# BOSS-Ion-Pump-Interface.net
KiCad netlist of a schematic drawn in EAGLE
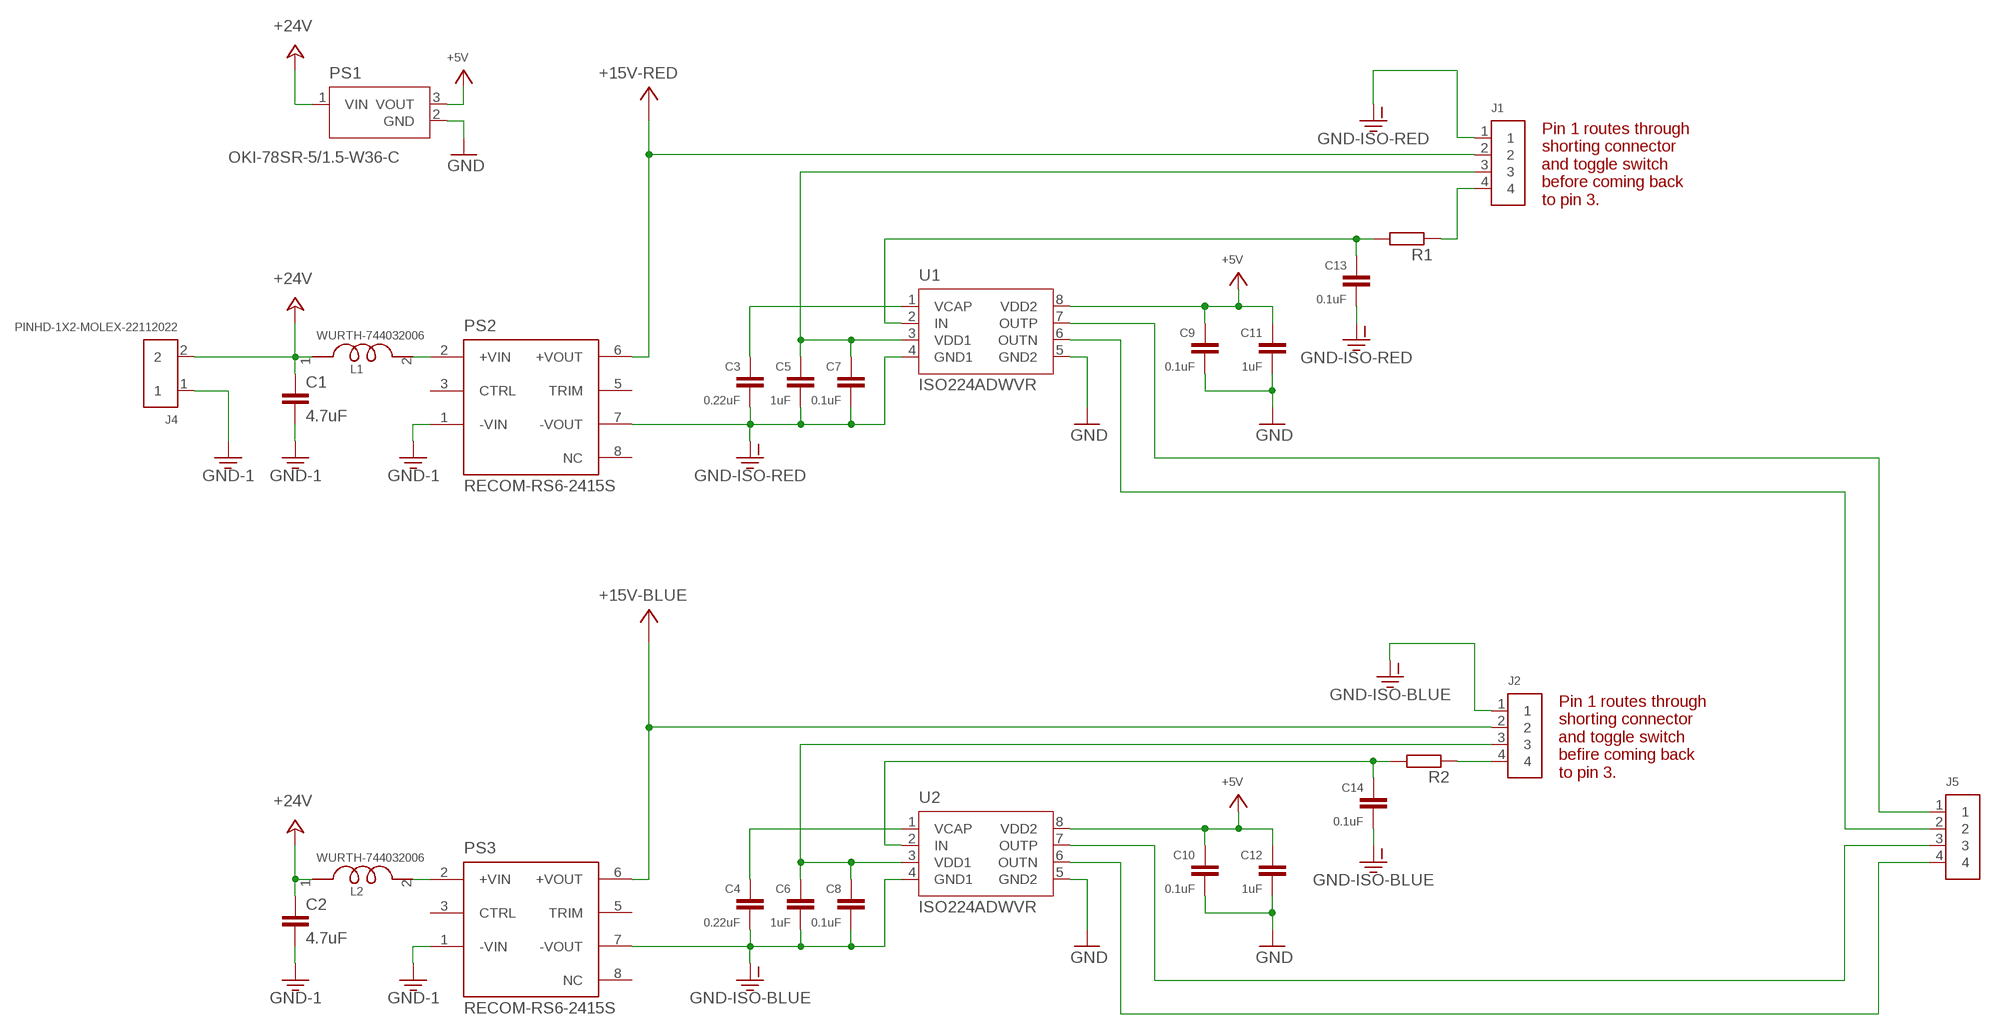
[diagram p0: schematic, sheet 1]

(export (version "E")
  (design (tool "Eeschema 10.0.6"))
  (components
    (comp (ref "C1")
      (value "4.7uF")
      (footprint "eagle-import:C1206")
      (libsource (lib "eagle-import") (part "C-EUC1206"))
    )
    (comp (ref "C2")
      (value "4.7uF")
      (footprint "eagle-import:C1206")
      (libsource (lib "eagle-import") (part "C-EUC1206"))
    )
    (comp (ref "C3")
      (value "0.22uF")
      (footprint "eagle-import:C0805")
      (libsource (lib "eagle-import") (part "C-EUC0805"))
    )
    (comp (ref "C4")
      (value "0.22uF")
      (footprint "eagle-import:C0805")
      (libsource (lib "eagle-import") (part "C-EUC0805"))
    )
    (comp (ref "C5")
      (value "1uF")
      (footprint "eagle-import:C0805")
      (libsource (lib "eagle-import") (part "C-EUC0805"))
    )
    (comp (ref "C6")
      (value "1uF")
      (footprint "eagle-import:C0805")
      (libsource (lib "eagle-import") (part "C-EUC0805"))
    )
    (comp (ref "C7")
      (value "0.1uF")
      (footprint "eagle-import:C0805")
      (libsource (lib "eagle-import") (part "C-EUC0805"))
    )
    (comp (ref "C8")
      (value "0.1uF")
      (footprint "eagle-import:C0805")
      (libsource (lib "eagle-import") (part "C-EUC0805"))
    )
    (comp (ref "C9")
      (value "0.1uF")
      (footprint "eagle-import:C0805")
      (libsource (lib "eagle-import") (part "C-EUC0805"))
    )
    (comp (ref "C10")
      (value "0.1uF")
      (footprint "eagle-import:C0805")
      (libsource (lib "eagle-import") (part "C-EUC0805"))
    )
    (comp (ref "C11")
      (value "1uF")
      (footprint "eagle-import:C0805")
      (libsource (lib "eagle-import") (part "C-EUC0805"))
    )
    (comp (ref "C12")
      (value "1uF")
      (footprint "eagle-import:C0805")
      (libsource (lib "eagle-import") (part "C-EUC0805"))
    )
    (comp (ref "C13")
      (value "0.1uF")
      (footprint "eagle-import:C0805")
      (libsource (lib "eagle-import") (part "C-EUC0805"))
    )
    (comp (ref "C14")
      (value "0.1uF")
      (footprint "eagle-import:C0805")
      (libsource (lib "eagle-import") (part "C-EUC0805"))
    )
    (comp (ref "J1")
      (value "PINHD-1X4-MOLEX-22112042")
      (footprint "eagle-import:1X04-MOLEX-22112042")
      (libsource (lib "eagle-import") (part "PINHD-1X4-MOLEX-22112042"))
    )
    (comp (ref "J2")
      (value "PINHD-1X4-MOLEX-22112042")
      (footprint "eagle-import:1X04-MOLEX-22112042")
      (libsource (lib "eagle-import") (part "PINHD-1X4-MOLEX-22112042"))
    )
    (comp (ref "J4")
      (value "PINHD-1X2-MOLEX-22112022")
      (footprint "eagle-import:1X02-MOLEX-22112022")
      (libsource (lib "eagle-import") (part "PINHD-1X2-MOLEX-22112022"))
    )
    (comp (ref "J5")
      (value "PINHD-1X4-MOLEX-22112042")
      (footprint "eagle-import:1X04-MOLEX-22112042")
      (libsource (lib "eagle-import") (part "PINHD-1X4-MOLEX-22112042"))
    )
    (comp (ref "L1")
      (value "WURTH-744032006")
      (footprint "eagle-import:WURTH-1210-INDUCTOR")
      (libsource (lib "eagle-import") (part "INDUCTOR-WURTH-744032006"))
    )
    (comp (ref "L2")
      (value "WURTH-744032006")
      (footprint "eagle-import:WURTH-1210-INDUCTOR")
      (libsource (lib "eagle-import") (part "INDUCTOR-WURTH-744032006"))
    )
    (comp (ref "PS1")
      (value "OKI-78SR-5/1.5-W36-C")
      (footprint "eagle-import:CONV_OKI-78SR-5_1.5-W36-C")
      (fields
        (field (name "DIGI-KEY_PART_NUMBER") "811-2196-5-ND")
        (field (name "MF") "Murata Power Solutions Inc.")
      )
      (libsource (lib "eagle-import") (part "OKI-78SR-5/1.5-W36-C"))
    )
    (comp (ref "PS2")
      (value "RECOM-RS6-2415S")
      (footprint "eagle-import:CONV_RS6-2415S")
      (fields
        (field (name "DIGI-KEY_PART_NUMBER") "945-2987-ND")
        (field (name "MF") "Recom Power")
        (field (name "MP") "RS6-2415S")
      )
      (libsource (lib "eagle-import") (part "DC-DC-15V-RECOM-RS6-2415S"))
    )
    (comp (ref "PS3")
      (value "RECOM-RS6-2415S")
      (footprint "eagle-import:CONV_RS6-2415S")
      (fields
        (field (name "DIGI-KEY_PART_NUMBER") "945-2987-ND")
        (field (name "MF") "Recom Power")
        (field (name "MP") "RS6-2415S")
      )
      (libsource (lib "eagle-import") (part "DC-DC-15V-RECOM-RS6-2415S"))
    )
    (comp (ref "R1")
      (value "R-EU_R0805")
      (footprint "eagle-import:R0805")
      (libsource (lib "eagle-import") (part "R-EU_R0805"))
    )
    (comp (ref "R2")
      (value "R-EU_R0805")
      (footprint "eagle-import:R0805")
      (libsource (lib "eagle-import") (part "R-EU_R0805"))
    )
    (comp (ref "U1")
      (value "ISO224ADWVR")
      (footprint "eagle-import:DWV8_TEX")
      (fields (field (name "COPYRIGHT") "Copyright (C) 2018 Accelerated Designs. All rights reserved"))
      (libsource (lib "eagle-import") (part "ISO224ADWVR"))
    )
    (comp (ref "U2")
      (value "ISO224ADWVR")
      (footprint "eagle-import:DWV8_TEX")
      (fields (field (name "COPYRIGHT") "Copyright (C) 2018 Accelerated Designs. All rights reserved"))
      (libsource (lib "eagle-import") (part "ISO224ADWVR"))
    )
  )
  (nets
    (net (code "1") (name "+5V") (class "Default")
      (node (ref "C10") (pin "1") (pinfunction "1_1") (pintype "passive"))
      (node (ref "C11") (pin "1") (pinfunction "1_1") (pintype "passive"))
      (node (ref "C12") (pin "1") (pinfunction "1_1") (pintype "passive"))
      (node (ref "C9") (pin "1") (pinfunction "1_1") (pintype "passive"))
      (node (ref "PS1") (pin "3") (pinfunction "VOUT_3") (pintype "power_in"))
      (node (ref "U1") (pin "8") (pinfunction "VDD2_8") (pintype "power_in"))
      (node (ref "U2") (pin "8") (pinfunction "VDD2_8") (pintype "power_in"))
    )
    (net (code "2") (name "+15V-BLUE") (class "Default")
      (node (ref "J2") (pin "2") (pinfunction "2_2") (pintype "bidirectional"))
      (node (ref "PS3") (pin "6") (pinfunction "+VOUT_6") (pintype "output"))
    )
    (net (code "3") (name "+15V-RED") (class "Default")
      (node (ref "J1") (pin "2") (pinfunction "2_2") (pintype "bidirectional"))
      (node (ref "PS2") (pin "6") (pinfunction "+VOUT_6") (pintype "output"))
    )
    (net (code "4") (name "+24V") (class "Default")
      (node (ref "C1") (pin "1") (pinfunction "1_1") (pintype "passive"))
      (node (ref "C2") (pin "1") (pinfunction "1_1") (pintype "passive"))
      (node (ref "J4") (pin "2") (pinfunction "2_2") (pintype "bidirectional"))
      (node (ref "L1") (pin "1") (pinfunction "1_1") (pintype "bidirectional"))
      (node (ref "L2") (pin "1") (pinfunction "1_1") (pintype "bidirectional"))
      (node (ref "PS1") (pin "1") (pinfunction "VIN_1") (pintype "input"))
    )
    (net (code "5") (name "GND") (class "Default")
      (node (ref "C10") (pin "2") (pinfunction "2_2") (pintype "passive"))
      (node (ref "C11") (pin "2") (pinfunction "2_2") (pintype "passive"))
      (node (ref "C12") (pin "2") (pinfunction "2_2") (pintype "passive"))
      (node (ref "C9") (pin "2") (pinfunction "2_2") (pintype "passive"))
      (node (ref "PS1") (pin "2") (pinfunction "GND_2") (pintype "power_in"))
      (node (ref "U1") (pin "5") (pinfunction "GND2_5") (pintype "power_in"))
      (node (ref "U2") (pin "5") (pinfunction "GND2_5") (pintype "power_in"))
    )
    (net (code "6") (name "GND-1") (class "Default")
      (node (ref "C1") (pin "2") (pinfunction "2_2") (pintype "passive"))
      (node (ref "C2") (pin "2") (pinfunction "2_2") (pintype "passive"))
      (node (ref "J4") (pin "1") (pinfunction "1_1") (pintype "bidirectional"))
      (node (ref "PS2") (pin "1") (pinfunction "-VIN_1") (pintype "input"))
      (node (ref "PS3") (pin "1") (pinfunction "-VIN_1") (pintype "input"))
    )
    (net (code "7") (name "GND-ISO-BLUE") (class "Default")
      (node (ref "C14") (pin "2") (pinfunction "2_2") (pintype "passive"))
      (node (ref "C4") (pin "2") (pinfunction "2_2") (pintype "passive"))
      (node (ref "C6") (pin "2") (pinfunction "2_2") (pintype "passive"))
      (node (ref "C8") (pin "2") (pinfunction "2_2") (pintype "passive"))
      (node (ref "J2") (pin "1") (pinfunction "1_1") (pintype "bidirectional"))
      (node (ref "PS3") (pin "7") (pinfunction "-VOUT_7") (pintype "output"))
      (node (ref "U2") (pin "4") (pinfunction "GND1_4") (pintype "power_in"))
    )
    (net (code "8") (name "GND-ISO-RED") (class "Default")
      (node (ref "C13") (pin "2") (pinfunction "2_2") (pintype "passive"))
      (node (ref "C3") (pin "2") (pinfunction "2_2") (pintype "passive"))
      (node (ref "C5") (pin "2") (pinfunction "2_2") (pintype "passive"))
      (node (ref "C7") (pin "2") (pinfunction "2_2") (pintype "passive"))
      (node (ref "J1") (pin "1") (pinfunction "1_1") (pintype "bidirectional"))
      (node (ref "PS2") (pin "7") (pinfunction "-VOUT_7") (pintype "output"))
      (node (ref "U1") (pin "4") (pinfunction "GND1_4") (pintype "power_in"))
    )
    (net (code "9") (name "Net-(J1-Pad4)") (class "Default")
      (node (ref "J1") (pin "4") (pinfunction "4_4") (pintype "bidirectional"))
      (node (ref "R1") (pin "1") (pinfunction "1_1") (pintype "passive"))
    )
    (net (code "10") (name "Net-(J2-Pad4)") (class "Default")
      (node (ref "J2") (pin "4") (pinfunction "4_4") (pintype "bidirectional"))
      (node (ref "R2") (pin "1") (pinfunction "1_1") (pintype "passive"))
    )
    (net (code "11") (name "Net-(PS2-+VIN)") (class "Default")
      (node (ref "L1") (pin "2") (pinfunction "2_2") (pintype "bidirectional"))
      (node (ref "PS2") (pin "2") (pinfunction "+VIN_2") (pintype "input"))
    )
    (net (code "12") (name "Net-(PS3-+VIN)") (class "Default")
      (node (ref "L2") (pin "2") (pinfunction "2_2") (pintype "bidirectional"))
      (node (ref "PS3") (pin "2") (pinfunction "+VIN_2") (pintype "input"))
    )
    (net (code "13") (name "Net-(U1-IN)") (class "Default")
      (node (ref "C13") (pin "1") (pinfunction "1_1") (pintype "passive"))
      (node (ref "R1") (pin "2") (pinfunction "2_2") (pintype "passive"))
      (node (ref "U1") (pin "2") (pinfunction "IN_2") (pintype "input"))
    )
    (net (code "14") (name "Net-(U1-OUTN)") (class "Default")
      (node (ref "J5") (pin "2") (pinfunction "2_2") (pintype "bidirectional"))
      (node (ref "U1") (pin "6") (pinfunction "OUTN_6") (pintype "output"))
    )
    (net (code "15") (name "Net-(U1-OUTP)") (class "Default")
      (node (ref "J5") (pin "1") (pinfunction "1_1") (pintype "bidirectional"))
      (node (ref "U1") (pin "7") (pinfunction "OUTP_7") (pintype "output"))
    )
    (net (code "16") (name "Net-(U1-VCAP)") (class "Default")
      (node (ref "C3") (pin "1") (pinfunction "1_1") (pintype "passive"))
      (node (ref "U1") (pin "1") (pinfunction "VCAP_1") (pintype "power_in"))
    )
    (net (code "17") (name "Net-(U1-VDD1)") (class "Default")
      (node (ref "C5") (pin "1") (pinfunction "1_1") (pintype "passive"))
      (node (ref "C7") (pin "1") (pinfunction "1_1") (pintype "passive"))
      (node (ref "J1") (pin "3") (pinfunction "3_3") (pintype "bidirectional"))
      (node (ref "U1") (pin "3") (pinfunction "VDD1_3") (pintype "power_in"))
    )
    (net (code "18") (name "Net-(U2-IN)") (class "Default")
      (node (ref "C14") (pin "1") (pinfunction "1_1") (pintype "passive"))
      (node (ref "R2") (pin "2") (pinfunction "2_2") (pintype "passive"))
      (node (ref "U2") (pin "2") (pinfunction "IN_2") (pintype "input"))
    )
    (net (code "19") (name "Net-(U2-OUTN)") (class "Default")
      (node (ref "J5") (pin "4") (pinfunction "4_4") (pintype "bidirectional"))
      (node (ref "U2") (pin "6") (pinfunction "OUTN_6") (pintype "output"))
    )
    (net (code "20") (name "Net-(U2-OUTP)") (class "Default")
      (node (ref "J5") (pin "3") (pinfunction "3_3") (pintype "bidirectional"))
      (node (ref "U2") (pin "7") (pinfunction "OUTP_7") (pintype "output"))
    )
    (net (code "21") (name "Net-(U2-VCAP)") (class "Default")
      (node (ref "C4") (pin "1") (pinfunction "1_1") (pintype "passive"))
      (node (ref "U2") (pin "1") (pinfunction "VCAP_1") (pintype "power_in"))
    )
    (net (code "22") (name "Net-(U2-VDD1)") (class "Default")
      (node (ref "C6") (pin "1") (pinfunction "1_1") (pintype "passive"))
      (node (ref "C8") (pin "1") (pinfunction "1_1") (pintype "passive"))
      (node (ref "J2") (pin "3") (pinfunction "3_3") (pintype "bidirectional"))
      (node (ref "U2") (pin "3") (pinfunction "VDD1_3") (pintype "power_in"))
    )
    (net (code "23") (name "unconnected-(PS2-CTRL-Pad3)") (class "Default")
      (node (ref "PS2") (pin "3") (pinfunction "CTRL_3") (pintype "input"))
    )
    (net (code "24") (name "unconnected-(PS2-NC-Pad8)") (class "Default")
      (node (ref "PS2") (pin "8") (pinfunction "NC_8") (pintype "no_connect"))
    )
    (net (code "25") (name "unconnected-(PS2-TRIM-Pad5)") (class "Default")
      (node (ref "PS2") (pin "5") (pinfunction "TRIM_5") (pintype "passive"))
    )
    (net (code "26") (name "unconnected-(PS3-CTRL-Pad3)") (class "Default")
      (node (ref "PS3") (pin "3") (pinfunction "CTRL_3") (pintype "input"))
    )
    (net (code "27") (name "unconnected-(PS3-NC-Pad8)") (class "Default")
      (node (ref "PS3") (pin "8") (pinfunction "NC_8") (pintype "no_connect"))
    )
    (net (code "28") (name "unconnected-(PS3-TRIM-Pad5)") (class "Default")
      (node (ref "PS3") (pin "5") (pinfunction "TRIM_5") (pintype "passive"))
    )
  )
)
